# etna-sch-connectors.net
KiCad netlist of a schematic drawn in Altium Designer
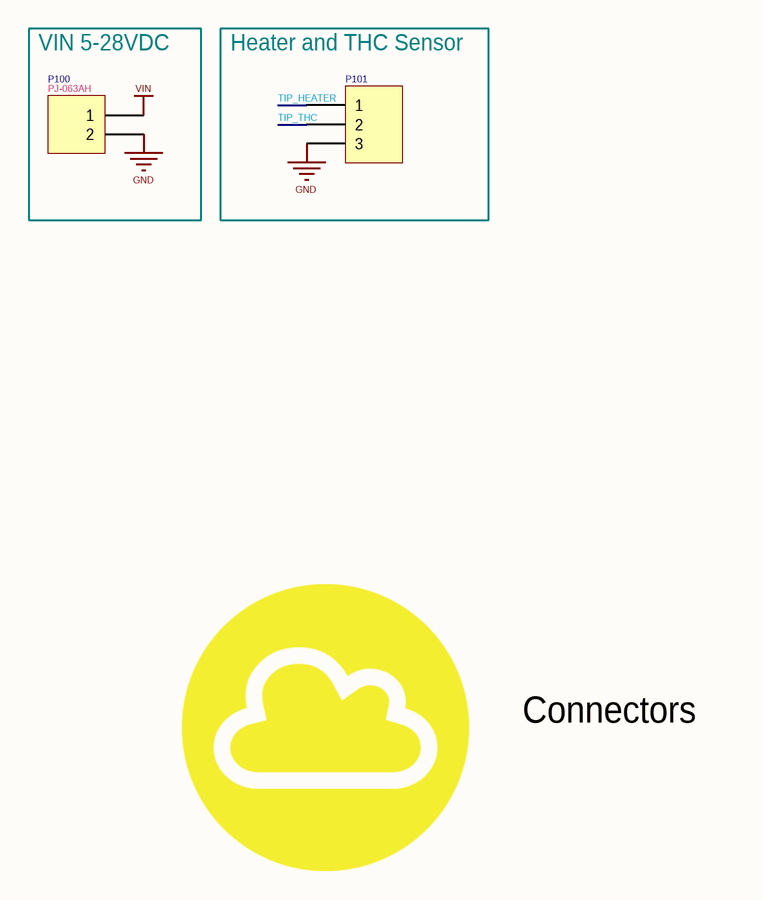
[diagram p0: etna-sch-connectors.SchDoc]

(export (version "E")
  (design (tool "Eeschema 10.0.6"))
  (components
    (comp (ref "P100")
      (value "PJ-063AH")
      (footprint "PJ-063AH")
      (description "Header, 2-Pin")
      (fields (field (name "PUBLISHER") "Altium Limited"))
      (libsource (lib "Miscellaneous Connectors") (part "Header 2"))
    )
    (comp (ref "P101")
      (value "~")
      (footprint "3x3x3")
      (description "Header, 3-Pin")
      (fields (field (name "PUBLISHER") "Altium Limited"))
      (libsource (lib "Miscellaneous Connectors") (part "Header 3"))
    )
  )
  (nets
    (net (code "1") (name "/TIP_HEATER") (class "Default")
      (node (ref "P101") (pin "1") (pinfunction "1_1") (pintype "passive"))
    )
    (net (code "2") (name "/TIP_THC") (class "Default")
      (node (ref "P101") (pin "2") (pinfunction "2_2") (pintype "passive"))
    )
    (net (code "3") (name "GND") (class "Default")
      (node (ref "P100") (pin "2") (pinfunction "2_2") (pintype "passive"))
      (node (ref "P101") (pin "3") (pinfunction "3_3") (pintype "passive"))
    )
    (net (code "4") (name "VIN") (class "Default")
      (node (ref "P100") (pin "1") (pinfunction "1_1") (pintype "passive"))
    )
  )
)
